# Game_of_Life_Lg_Screen_v1.net
KiCad netlist of a schematic drawn in EAGLE
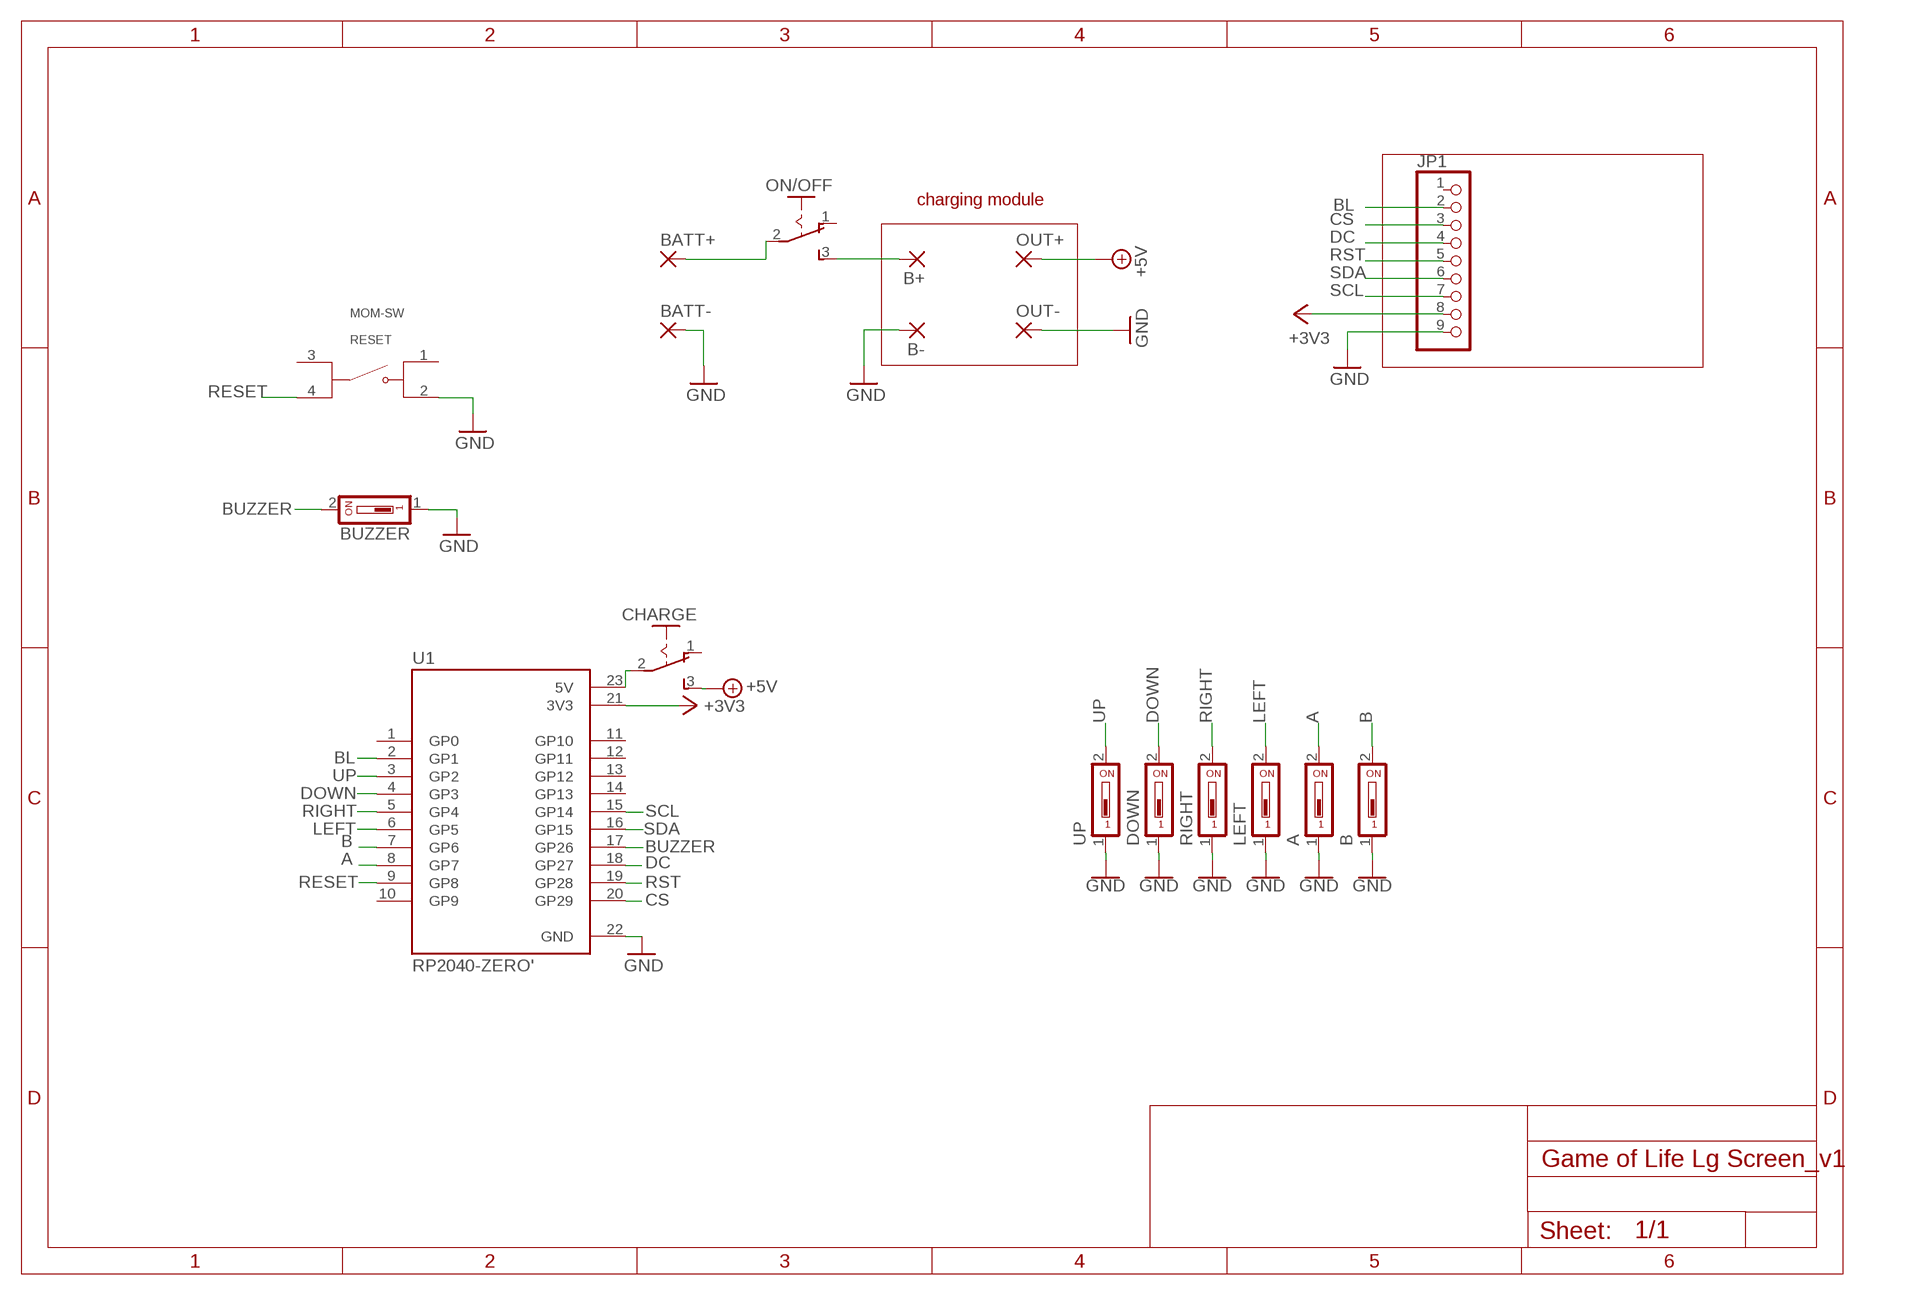
[diagram p0: schematic, sheet 1]

(export (version "E")
  (design (tool "Eeschema 10.0.6"))
  (components
    (comp (ref "A")
      (value "DS01")
      (footprint "eagle-import:DS-01")
      (libsource (lib "eagle-import") (part "DS01"))
    )
    (comp (ref "B")
      (value "DS01")
      (footprint "eagle-import:DS-01")
      (libsource (lib "eagle-import") (part "DS01"))
    )
    (comp (ref "B+")
      (value "SMD5")
      (footprint "eagle-import:SMD2,54-5,08")
      (libsource (lib "eagle-import") (part "SMD5"))
    )
    (comp (ref "B-")
      (value "SMD5")
      (footprint "eagle-import:SMD2,54-5,08")
      (libsource (lib "eagle-import") (part "SMD5"))
    )
    (comp (ref "BATT+")
      (value "SMD5")
      (footprint "eagle-import:SMD2,54-5,08")
      (libsource (lib "eagle-import") (part "SMD5"))
    )
    (comp (ref "BATT-")
      (value "SMD5")
      (footprint "eagle-import:SMD2,54-5,08")
      (libsource (lib "eagle-import") (part "SMD5"))
    )
    (comp (ref "BUZZER")
      (value "DS01")
      (footprint "eagle-import:DS-01")
      (libsource (lib "eagle-import") (part "buzzer_DS01"))
    )
    (comp (ref "CHARGE")
      (value "M251")
      (footprint "eagle-import:M251")
      (libsource (lib "eagle-import") (part "M251"))
    )
    (comp (ref "DOWN")
      (value "DS01")
      (footprint "eagle-import:DS-01")
      (libsource (lib "eagle-import") (part "DS01"))
    )
    (comp (ref "JP1")
      (value "PINHD-1X9")
      (footprint "eagle-import:1X09")
      (libsource (lib "eagle-import") (part "PINHD-1X9"))
    )
    (comp (ref "LEFT")
      (value "DS01")
      (footprint "eagle-import:DS-01")
      (libsource (lib "eagle-import") (part "DS01"))
    )
    (comp (ref "ON/OFF")
      (value "M251")
      (footprint "eagle-import:M251")
      (libsource (lib "eagle-import") (part "M251"))
    )
    (comp (ref "OUT+")
      (value "SMD5")
      (footprint "eagle-import:SMD2,54-5,08")
      (libsource (lib "eagle-import") (part "SMD5"))
    )
    (comp (ref "OUT-")
      (value "SMD5")
      (footprint "eagle-import:SMD2,54-5,08")
      (libsource (lib "eagle-import") (part "SMD5"))
    )
    (comp (ref "RESET")
      (value "MOM-SW")
      (footprint "eagle-import:SW_TS18-5-25-SL-260-SMT-TR")
      (fields (field (name "MF") "Same Sky") (field (name "MP") "TS18-5-25-SL-260-SMT-TR"))
      (libsource (lib "eagle-import") (part "TS18-5-25-SL-260-SMT-TR"))
    )
    (comp (ref "RIGHT")
      (value "DS01")
      (footprint "eagle-import:DS-01")
      (libsource (lib "eagle-import") (part "DS01"))
    )
    (comp (ref "U1")
      (value "RP2040-ZERO'")
      (footprint "eagle-import:MODULE_RP2040-ZERO")
      (fields (field (name "MF") "Waveshare Electronics") (field (name "MP") "RP2040-ZERO"))
      (libsource (lib "eagle-import") (part "RP2040-ZERO'"))
    )
    (comp (ref "UP")
      (value "DS01")
      (footprint "eagle-import:DS-01")
      (libsource (lib "eagle-import") (part "DS01"))
    )
  )
  (nets
    (net (code "1") (name "+3V3") (class "Default")
      (node (ref "JP1") (pin "8") (pinfunction "8_8") (pintype "passive"))
      (node (ref "U1") (pin "21") (pinfunction "3V3_21") (pintype "power_in"))
    )
    (net (code "2") (name "+5V") (class "Default")
      (node (ref "CHARGE") (pin "3") (pinfunction "S_3") (pintype "passive"))
      (node (ref "OUT+") (pin "1") (pinfunction "P_1") (pintype "passive"))
    )
    (net (code "3") (name "/A") (class "Default")
      (node (ref "A") (pin "2") (pinfunction "2_2") (pintype "passive"))
      (node (ref "U1") (pin "8") (pinfunction "GP7_8") (pintype "bidirectional"))
    )
    (net (code "4") (name "/B") (class "Default")
      (node (ref "B") (pin "2") (pinfunction "2_2") (pintype "passive"))
      (node (ref "U1") (pin "7") (pinfunction "GP6_7") (pintype "bidirectional"))
    )
    (net (code "5") (name "/BL") (class "Default")
      (node (ref "JP1") (pin "2") (pinfunction "2_2") (pintype "passive"))
      (node (ref "U1") (pin "2") (pinfunction "GP1_2") (pintype "bidirectional"))
    )
    (net (code "6") (name "/BUZZER") (class "Default")
      (node (ref "BUZZER") (pin "2") (pinfunction "2_2") (pintype "passive"))
      (node (ref "U1") (pin "17") (pinfunction "GP26_17") (pintype "bidirectional"))
    )
    (net (code "7") (name "/CS") (class "Default")
      (node (ref "JP1") (pin "3") (pinfunction "3_3") (pintype "passive"))
      (node (ref "U1") (pin "20") (pinfunction "GP29_20") (pintype "bidirectional"))
    )
    (net (code "8") (name "/DC") (class "Default")
      (node (ref "JP1") (pin "4") (pinfunction "4_4") (pintype "passive"))
      (node (ref "U1") (pin "18") (pinfunction "GP27_18") (pintype "bidirectional"))
    )
    (net (code "9") (name "/DOWN") (class "Default")
      (node (ref "DOWN") (pin "2") (pinfunction "2_2") (pintype "passive"))
      (node (ref "U1") (pin "4") (pinfunction "GP3_4") (pintype "bidirectional"))
    )
    (net (code "10") (name "/LEFT") (class "Default")
      (node (ref "LEFT") (pin "2") (pinfunction "2_2") (pintype "passive"))
      (node (ref "U1") (pin "6") (pinfunction "GP5_6") (pintype "bidirectional"))
    )
    (net (code "11") (name "/RESET") (class "Default")
      (node (ref "RESET") (pin "4") (pinfunction "4_4") (pintype "passive"))
      (node (ref "U1") (pin "9") (pinfunction "GP8_9") (pintype "bidirectional"))
    )
    (net (code "12") (name "/RIGHT") (class "Default")
      (node (ref "RIGHT") (pin "2") (pinfunction "2_2") (pintype "passive"))
      (node (ref "U1") (pin "5") (pinfunction "GP4_5") (pintype "bidirectional"))
    )
    (net (code "13") (name "/RST") (class "Default")
      (node (ref "JP1") (pin "5") (pinfunction "5_5") (pintype "passive"))
      (node (ref "U1") (pin "19") (pinfunction "GP28_19") (pintype "bidirectional"))
    )
    (net (code "14") (name "/SCL") (class "Default")
      (node (ref "JP1") (pin "7") (pinfunction "7_7") (pintype "passive"))
      (node (ref "U1") (pin "15") (pinfunction "GP14_15") (pintype "bidirectional"))
    )
    (net (code "15") (name "/SDA") (class "Default")
      (node (ref "JP1") (pin "6") (pinfunction "6_6") (pintype "passive"))
      (node (ref "U1") (pin "16") (pinfunction "GP15_16") (pintype "bidirectional"))
    )
    (net (code "16") (name "/UP") (class "Default")
      (node (ref "U1") (pin "3") (pinfunction "GP2_3") (pintype "bidirectional"))
      (node (ref "UP") (pin "2") (pinfunction "2_2") (pintype "passive"))
    )
    (net (code "17") (name "GND") (class "Default")
      (node (ref "A") (pin "1") (pinfunction "1_1") (pintype "passive"))
      (node (ref "B") (pin "1") (pinfunction "1_1") (pintype "passive"))
      (node (ref "B-") (pin "1") (pinfunction "P_1") (pintype "passive"))
      (node (ref "BATT-") (pin "1") (pinfunction "P_1") (pintype "passive"))
      (node (ref "BUZZER") (pin "1") (pinfunction "1_1") (pintype "passive"))
      (node (ref "DOWN") (pin "1") (pinfunction "1_1") (pintype "passive"))
      (node (ref "JP1") (pin "9") (pinfunction "9_9") (pintype "passive"))
      (node (ref "LEFT") (pin "1") (pinfunction "1_1") (pintype "passive"))
      (node (ref "OUT-") (pin "1") (pinfunction "P_1") (pintype "passive"))
      (node (ref "RESET") (pin "2") (pinfunction "2_2") (pintype "passive"))
      (node (ref "RIGHT") (pin "1") (pinfunction "1_1") (pintype "passive"))
      (node (ref "U1") (pin "22") (pinfunction "GND_22") (pintype "power_in"))
      (node (ref "UP") (pin "1") (pinfunction "1_1") (pintype "passive"))
    )
    (net (code "18") (name "Net-(B+-P)") (class "Default")
      (node (ref "B+") (pin "1") (pinfunction "P_1") (pintype "passive"))
      (node (ref "ON/OFF") (pin "3") (pinfunction "S_3") (pintype "passive"))
    )
    (net (code "19") (name "Net-(BATT+-P)") (class "Default")
      (node (ref "BATT+") (pin "1") (pinfunction "P_1") (pintype "passive"))
      (node (ref "ON/OFF") (pin "2") (pinfunction "P_2") (pintype "passive"))
    )
    (net (code "20") (name "Net-(CHARGE-P)") (class "Default")
      (node (ref "CHARGE") (pin "2") (pinfunction "P_2") (pintype "passive"))
      (node (ref "U1") (pin "23") (pinfunction "5V_23") (pintype "power_in"))
    )
    (net (code "21") (name "unconnected-(CHARGE-O-Pad1)") (class "Default")
      (node (ref "CHARGE") (pin "1") (pinfunction "O_1") (pintype "passive"))
    )
    (net (code "22") (name "unconnected-(JP1-Pad1)") (class "Default")
      (node (ref "JP1") (pin "1") (pinfunction "1_1") (pintype "passive"))
    )
    (net (code "23") (name "unconnected-(ON/OFF-O-Pad1)") (class "Default")
      (node (ref "ON/OFF") (pin "1") (pinfunction "O_1") (pintype "passive"))
    )
    (net (code "24") (name "unconnected-(RESET-Pad1)") (class "Default")
      (node (ref "RESET") (pin "1") (pinfunction "1_1") (pintype "passive"))
    )
    (net (code "25") (name "unconnected-(RESET-Pad3)") (class "Default")
      (node (ref "RESET") (pin "3") (pinfunction "3_3") (pintype "passive"))
    )
    (net (code "26") (name "unconnected-(U1-GP0-Pad1)") (class "Default")
      (node (ref "U1") (pin "1") (pinfunction "GP0_1") (pintype "bidirectional"))
    )
    (net (code "27") (name "unconnected-(U1-GP9-Pad10)") (class "Default")
      (node (ref "U1") (pin "10") (pinfunction "GP9_10") (pintype "bidirectional"))
    )
    (net (code "28") (name "unconnected-(U1-GP10-Pad11)") (class "Default")
      (node (ref "U1") (pin "11") (pinfunction "GP10_11") (pintype "bidirectional"))
    )
    (net (code "29") (name "unconnected-(U1-GP11-Pad12)") (class "Default")
      (node (ref "U1") (pin "12") (pinfunction "GP11_12") (pintype "bidirectional"))
    )
    (net (code "30") (name "unconnected-(U1-GP12-Pad13)") (class "Default")
      (node (ref "U1") (pin "13") (pinfunction "GP12_13") (pintype "bidirectional"))
    )
    (net (code "31") (name "unconnected-(U1-GP13-Pad14)") (class "Default")
      (node (ref "U1") (pin "14") (pinfunction "GP13_14") (pintype "bidirectional"))
    )
  )
)
